# espurna-wd.net
KiCad netlist of a schematic drawn in EAGLE
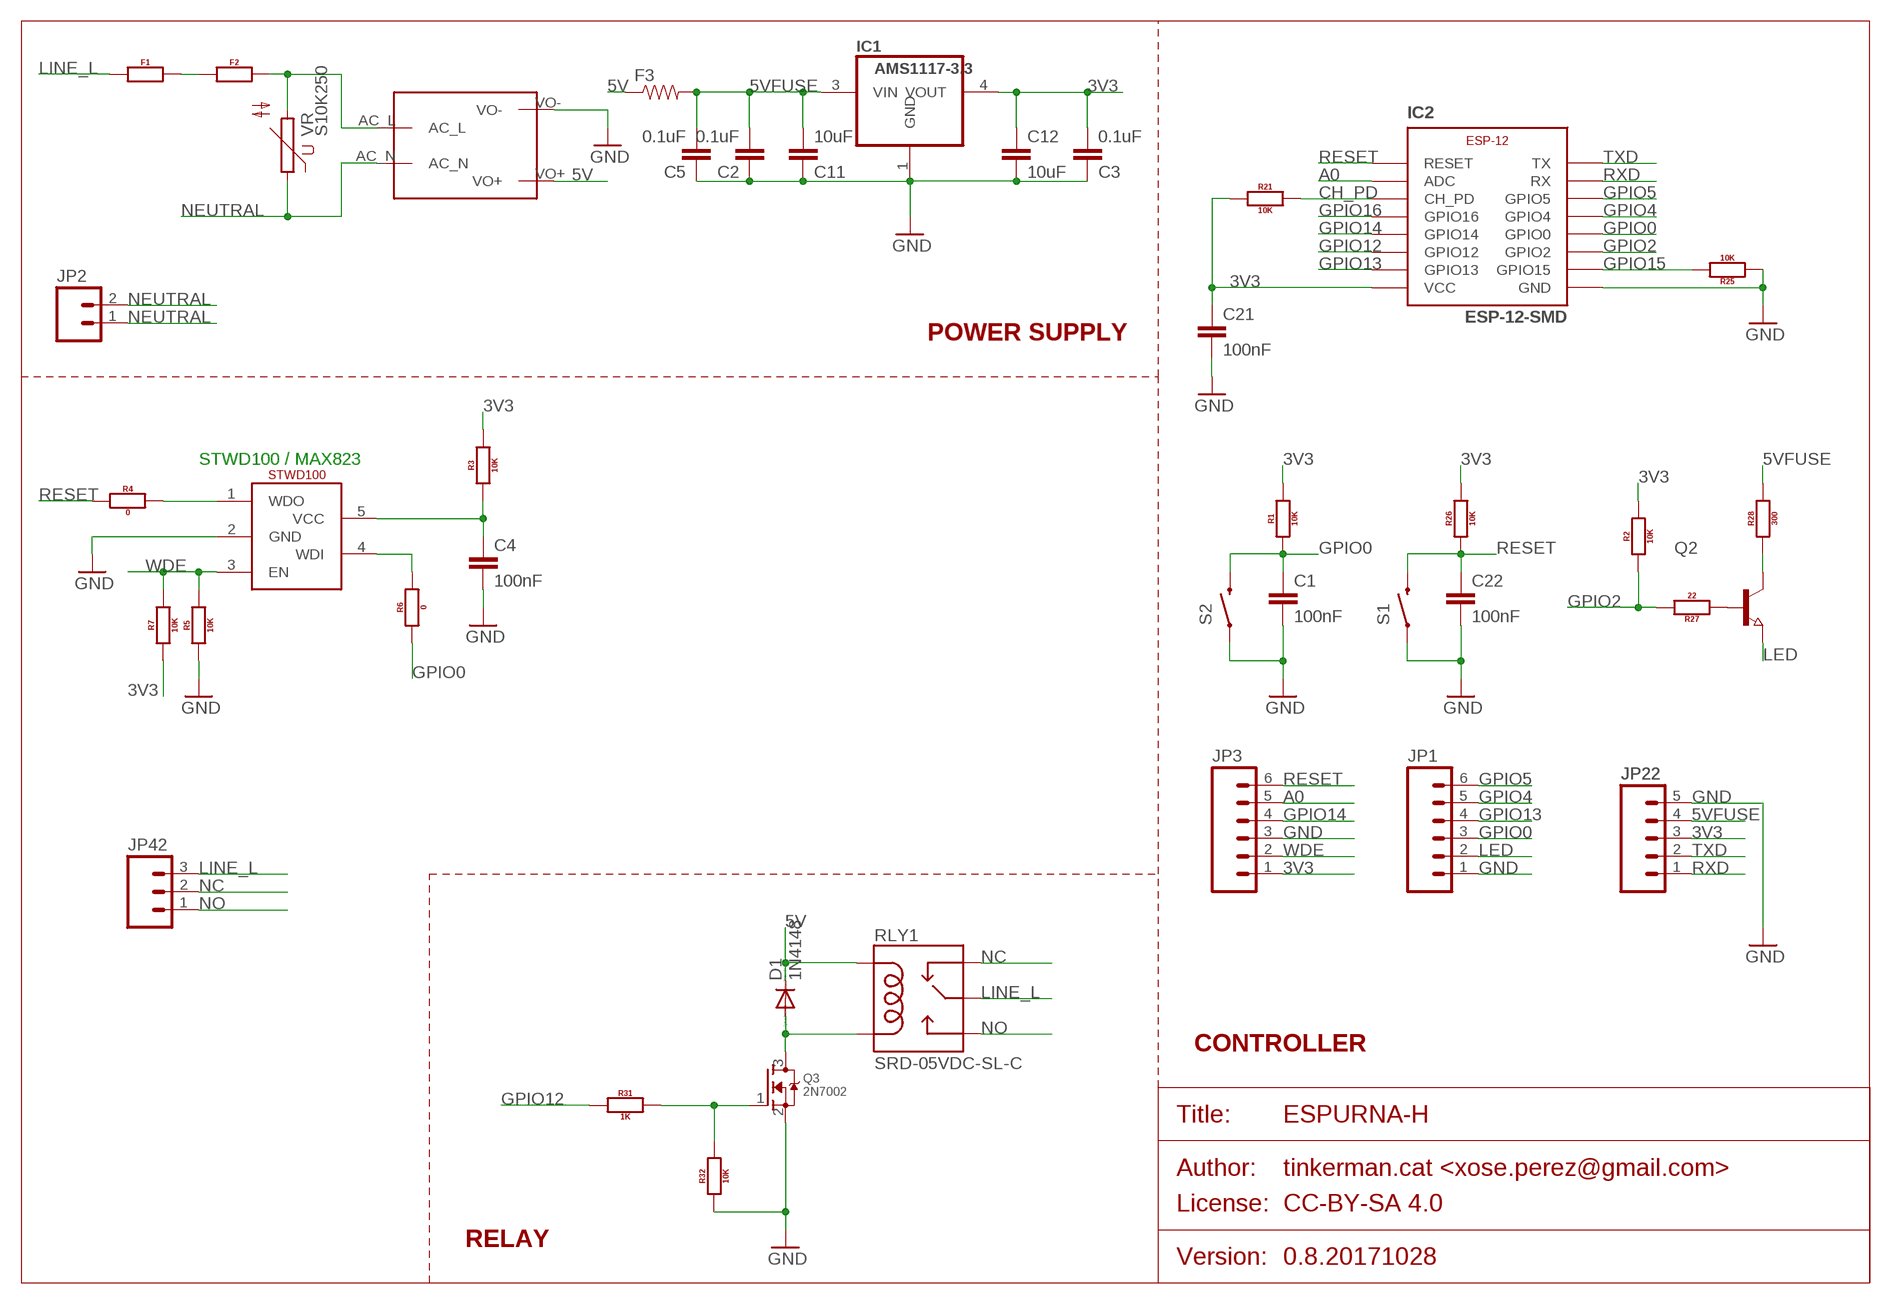
[diagram p0: schematic, sheet 1]

(export (version "E")
  (design (tool "Eeschema 10.0.6"))
  (components
    (comp (ref "C1")
      (value "100nF")
      (footprint "eagle-import:0805")
      (libsource (lib "eagle-import") (part "C-EU0805"))
    )
    (comp (ref "C2")
      (value "0.1uF")
      (footprint "eagle-import:C1206K")
      (libsource (lib "eagle-import") (part "C-EUC1206K"))
    )
    (comp (ref "C3")
      (value "0.1uF")
      (footprint "eagle-import:0805")
      (libsource (lib "eagle-import") (part "C-EU0805"))
    )
    (comp (ref "C4")
      (value "100nF")
      (footprint "eagle-import:0805")
      (libsource (lib "eagle-import") (part "C-EU0805"))
    )
    (comp (ref "C5")
      (value "0.1uF")
      (footprint "eagle-import:0805")
      (libsource (lib "eagle-import") (part "C-EU0805"))
    )
    (comp (ref "C11")
      (value "10uF")
      (footprint "eagle-import:C1206K")
      (libsource (lib "eagle-import") (part "C-EUC1206K"))
    )
    (comp (ref "C12")
      (value "10uF")
      (footprint "eagle-import:C1206")
      (libsource (lib "eagle-import") (part "C-EUC1206"))
    )
    (comp (ref "C21")
      (value "100nF")
      (footprint "eagle-import:0805")
      (libsource (lib "eagle-import") (part "C-EU0805"))
    )
    (comp (ref "C22")
      (value "100nF")
      (footprint "eagle-import:0805")
      (libsource (lib "eagle-import") (part "C-EU0805"))
    )
    (comp (ref "D1")
      (value "1N4148")
      (footprint "eagle-import:DO214BA")
      (libsource (lib "eagle-import") (part "DIODE-DO214BA"))
    )
    (comp (ref "F1")
      (value "THERMALFUSE0.4")
      (footprint "eagle-import:AXIAL-0.4")
      (libsource (lib "eagle-import") (part "THERMALFUSE0.4"))
    )
    (comp (ref "F2")
      (value "THERMALFUSE0.4")
      (footprint "eagle-import:AXIAL-0.4")
      (libsource (lib "eagle-import") (part "THERMALFUSE0.4"))
    )
    (comp (ref "F3")
      (value "RESISTOR1206")
      (footprint "eagle-import:1206")
      (libsource (lib "eagle-import") (part "RESISTOR1206"))
    )
    (comp (ref "IC1")
      (value "AMS1117-3.3")
      (footprint "eagle-import:SOT223")
      (libsource (lib "eagle-import") (part "REG1117SOT223-2"))
    )
    (comp (ref "IC2")
      (value "ESP-12-SMD")
      (footprint "eagle-import:ESP-12-SMD")
      (libsource (lib "eagle-import") (part "ESP-12-SMD"))
    )
    (comp (ref "JP1")
      (value "M06NO_SILK_FEMALE_PTH")
      (footprint "eagle-import:1X06_NO_SILK")
      (libsource (lib "eagle-import") (part "M06NO_SILK_FEMALE_PTH"))
    )
    (comp (ref "JP2")
      (value "M02200MIL")
      (footprint "eagle-import:SCREWTERMINAL-200MIL-2")
      (libsource (lib "eagle-import") (part "M02200MIL"))
    )
    (comp (ref "JP3")
      (value "M06NO_SILK_FEMALE_PTH")
      (footprint "eagle-import:1X06_NO_SILK")
      (libsource (lib "eagle-import") (part "M06NO_SILK_FEMALE_PTH"))
    )
    (comp (ref "JP22")
      (value "M05PTH")
      (footprint "eagle-import:1X05")
      (libsource (lib "eagle-import") (part "M05PTH"))
    )
    (comp (ref "JP42")
      (value "M03200MIL")
      (footprint "eagle-import:SCREWTERMINAL-200MIL-3")
      (libsource (lib "eagle-import") (part "M03200MIL"))
    )
    (comp (ref "Q2")
      (value "NPN-TRANSISTOR_SOT23")
      (footprint "eagle-import:SOT23")
      (libsource (lib "eagle-import") (part "NPN-TRANSISTOR_SOT23"))
    )
    (comp (ref "Q3")
      (value "2N7002")
      (footprint "eagle-import:SOT23")
      (libsource (lib "eagle-import") (part "MOSFET-NREFLOW"))
    )
    (comp (ref "R1")
      (value "10K")
      (footprint "eagle-import:0805")
      (libsource (lib "eagle-import") (part "RESISTOR0805"))
    )
    (comp (ref "R2")
      (value "10K")
      (footprint "eagle-import:0805")
      (libsource (lib "eagle-import") (part "RESISTOR0805"))
    )
    (comp (ref "R3")
      (value "10K")
      (footprint "eagle-import:0805")
      (libsource (lib "eagle-import") (part "RESISTOR0805"))
    )
    (comp (ref "R4")
      (value "0")
      (footprint "eagle-import:0805")
      (libsource (lib "eagle-import") (part "RESISTOR0805"))
    )
    (comp (ref "R5")
      (value "10K")
      (footprint "eagle-import:0805")
      (libsource (lib "eagle-import") (part "RESISTOR0805"))
    )
    (comp (ref "R6")
      (value "0")
      (footprint "eagle-import:0805")
      (libsource (lib "eagle-import") (part "RESISTOR0805"))
    )
    (comp (ref "R7")
      (value "10K")
      (footprint "eagle-import:0805")
      (libsource (lib "eagle-import") (part "RESISTOR0805"))
    )
    (comp (ref "R21")
      (value "10K")
      (footprint "eagle-import:0805")
      (libsource (lib "eagle-import") (part "RESISTOR0805"))
    )
    (comp (ref "R25")
      (value "10K")
      (footprint "eagle-import:0805")
      (libsource (lib "eagle-import") (part "RESISTOR0805"))
    )
    (comp (ref "R26")
      (value "10K")
      (footprint "eagle-import:0805")
      (libsource (lib "eagle-import") (part "RESISTOR0805"))
    )
    (comp (ref "R27")
      (value "22")
      (footprint "eagle-import:0805")
      (libsource (lib "eagle-import") (part "RESISTOR0805"))
    )
    (comp (ref "R28")
      (value "300")
      (footprint "eagle-import:0805")
      (libsource (lib "eagle-import") (part "RESISTOR0805"))
    )
    (comp (ref "R31")
      (value "1K")
      (footprint "eagle-import:0805")
      (libsource (lib "eagle-import") (part "RESISTOR0805"))
    )
    (comp (ref "R32")
      (value "10K")
      (footprint "eagle-import:0805")
      (libsource (lib "eagle-import") (part "RESISTOR0805"))
    )
    (comp (ref "RLY1")
      (value "SRD-05VDC-SL-C")
      (footprint "eagle-import:SRD-5VDC-SL-C")
      (libsource (lib "eagle-import") (part "RELAYSONGLE"))
    )
    (comp (ref "S1")
      (value "SWITCH-MOMENTARY-2SMD-1101NE")
      (footprint "eagle-import:TACTILE-SWITCH-1101NE")
      (libsource (lib "eagle-import") (part "SWITCH-MOMENTARY-2SMD-1101NE"))
    )
    (comp (ref "S2")
      (value "SWITCH-MOMENTARY-2SMD-1101NE")
      (footprint "eagle-import:TACTILE-SWITCH-1101NE")
      (libsource (lib "eagle-import") (part "SWITCH-MOMENTARY-2SMD-1101NE"))
    )
    (comp (ref "U$1")
      (value "MAINS_CONVERTERS")
      (footprint "eagle-import:HLK-PM01")
      (libsource (lib "eagle-import") (part "MAINS_CONVERTERS"))
    )
    (comp (ref "VR")
      (value "S10K250")
      (footprint "eagle-import:S10K250")
      (libsource (lib "eagle-import") (part "S10K250"))
    )
    (comp (ref "WD")
      (value "STWD100")
      (footprint "eagle-import:SOT95P280X145-5N")
      (libsource (lib "eagle-import") (part "STWD100"))
    )
  )
  (nets
    (net (code "1") (name "/3V3") (class "Default")
      (node (ref "C12") (pin "1") (pinfunction "1_1") (pintype "passive"))
      (node (ref "C21") (pin "1") (pinfunction "1_1") (pintype "passive"))
      (node (ref "C3") (pin "2") (pinfunction "2_2") (pintype "passive"))
      (node (ref "IC1") (pin "4") (pinfunction "VOUT_4") (pintype "output"))
      (node (ref "IC2") (pin "VCC") (pinfunction "VCC_VCC") (pintype "bidirectional"))
      (node (ref "JP22") (pin "3") (pinfunction "3_3") (pintype "passive"))
      (node (ref "JP3") (pin "1") (pinfunction "1_1") (pintype "passive"))
      (node (ref "R1") (pin "2") (pinfunction "2_2") (pintype "passive"))
      (node (ref "R2") (pin "2") (pinfunction "2_2") (pintype "passive"))
      (node (ref "R21") (pin "1") (pinfunction "1_1") (pintype "passive"))
      (node (ref "R26") (pin "2") (pinfunction "2_2") (pintype "passive"))
      (node (ref "R3") (pin "2") (pinfunction "2_2") (pintype "passive"))
      (node (ref "R7") (pin "1") (pinfunction "1_1") (pintype "passive"))
    )
    (net (code "2") (name "/5V") (class "Default")
      (node (ref "D1") (pin "C") (pinfunction "C_C") (pintype "passive"))
      (node (ref "F3") (pin "1") (pinfunction "1_1") (pintype "passive"))
      (node (ref "RLY1") (pin "COIL1") (pinfunction "COIL1_COIL1") (pintype "bidirectional"))
      (node (ref "U$1") (pin "VO+") (pinfunction "VO+_VO+") (pintype "output"))
    )
    (net (code "3") (name "/5VFUSE") (class "Default")
      (node (ref "C11") (pin "2") (pinfunction "2_2") (pintype "passive"))
      (node (ref "C2") (pin "2") (pinfunction "2_2") (pintype "passive"))
      (node (ref "C5") (pin "2") (pinfunction "2_2") (pintype "passive"))
      (node (ref "F3") (pin "2") (pinfunction "2_2") (pintype "passive"))
      (node (ref "IC1") (pin "3") (pinfunction "VIN_3") (pintype "input"))
      (node (ref "JP22") (pin "4") (pinfunction "4_4") (pintype "passive"))
      (node (ref "R28") (pin "2") (pinfunction "2_2") (pintype "passive"))
    )
    (net (code "4") (name "/A0") (class "Default")
      (node (ref "IC2") (pin "ADC") (pinfunction "ADC_ADC") (pintype "bidirectional"))
      (node (ref "JP3") (pin "5") (pinfunction "5_5") (pintype "passive"))
    )
    (net (code "5") (name "/CH_PD") (class "Default")
      (node (ref "IC2") (pin "CH_PD") (pinfunction "CH_PD_CH_PD") (pintype "bidirectional"))
      (node (ref "R21") (pin "2") (pinfunction "2_2") (pintype "passive"))
    )
    (net (code "6") (name "/GPIO0") (class "Default")
      (node (ref "C1") (pin "1") (pinfunction "1_1") (pintype "passive"))
      (node (ref "IC2") (pin "GPIO0") (pinfunction "GPIO0_GPIO0") (pintype "bidirectional"))
      (node (ref "JP1") (pin "3") (pinfunction "3_3") (pintype "passive"))
      (node (ref "R1") (pin "1") (pinfunction "1_1") (pintype "passive"))
      (node (ref "R6") (pin "1") (pinfunction "1_1") (pintype "passive"))
      (node (ref "S2") (pin "2") (pinfunction "2_2") (pintype "passive"))
    )
    (net (code "7") (name "/GPIO2") (class "Default")
      (node (ref "IC2") (pin "GPIO2") (pinfunction "GPIO2_GPIO2") (pintype "bidirectional"))
      (node (ref "R2") (pin "1") (pinfunction "1_1") (pintype "passive"))
      (node (ref "R27") (pin "2") (pinfunction "2_2") (pintype "passive"))
    )
    (net (code "8") (name "/GPIO4") (class "Default")
      (node (ref "IC2") (pin "GPIO4") (pinfunction "GPIO4_GPIO4") (pintype "bidirectional"))
      (node (ref "JP1") (pin "5") (pinfunction "5_5") (pintype "passive"))
    )
    (net (code "9") (name "/GPIO5") (class "Default")
      (node (ref "IC2") (pin "GPIO5") (pinfunction "GPIO5_GPIO5") (pintype "bidirectional"))
      (node (ref "JP1") (pin "6") (pinfunction "6_6") (pintype "passive"))
    )
    (net (code "10") (name "/GPIO12") (class "Default")
      (node (ref "IC2") (pin "GPIO12") (pinfunction "GPIO12_GPIO12") (pintype "bidirectional"))
      (node (ref "R31") (pin "1") (pinfunction "1_1") (pintype "passive"))
    )
    (net (code "11") (name "/GPIO13") (class "Default")
      (node (ref "IC2") (pin "GPIO13") (pinfunction "GPIO13_GPIO13") (pintype "bidirectional"))
      (node (ref "JP1") (pin "4") (pinfunction "4_4") (pintype "passive"))
    )
    (net (code "12") (name "/GPIO14") (class "Default")
      (node (ref "IC2") (pin "GPIO14") (pinfunction "GPIO14_GPIO14") (pintype "bidirectional"))
      (node (ref "JP3") (pin "4") (pinfunction "4_4") (pintype "passive"))
    )
    (net (code "13") (name "/GPIO15") (class "Default")
      (node (ref "IC2") (pin "GPIO15") (pinfunction "GPIO15_GPIO15") (pintype "bidirectional"))
      (node (ref "R25") (pin "2") (pinfunction "2_2") (pintype "passive"))
    )
    (net (code "14") (name "/GPIO16") (class "Default")
      (node (ref "IC2") (pin "GPIO16") (pinfunction "GPIO16_GPIO16") (pintype "bidirectional"))
    )
    (net (code "15") (name "/LED") (class "Default")
      (node (ref "JP1") (pin "2") (pinfunction "2_2") (pintype "passive"))
      (node (ref "Q2") (pin "2") (pinfunction "E_2") (pintype "passive"))
    )
    (net (code "16") (name "/LINE_L") (class "Default")
      (node (ref "F1") (pin "P$1") (pinfunction "1_P$1") (pintype "passive"))
      (node (ref "JP42") (pin "3") (pinfunction "3_3") (pintype "passive"))
      (node (ref "RLY1") (pin "COMMON") (pinfunction "MAIN_COMMON") (pintype "bidirectional"))
    )
    (net (code "17") (name "/NC") (class "Default")
      (node (ref "JP42") (pin "2") (pinfunction "2_2") (pintype "passive"))
      (node (ref "RLY1") (pin "CLOSED") (pinfunction "NC_CLOSED") (pintype "bidirectional"))
    )
    (net (code "18") (name "/NEUTRAL") (class "Default")
      (node (ref "JP2") (pin "1") (pinfunction "1_1") (pintype "passive"))
      (node (ref "JP2") (pin "2") (pinfunction "2_2") (pintype "passive"))
      (node (ref "U$1") (pin "AC_N") (pinfunction "AC_N_AC_N") (pintype "input"))
      (node (ref "VR") (pin "1") (pinfunction "1_1") (pintype "passive"))
    )
    (net (code "19") (name "/NO") (class "Default")
      (node (ref "JP42") (pin "1") (pinfunction "1_1") (pintype "passive"))
      (node (ref "RLY1") (pin "OPEN") (pinfunction "NO_OPEN") (pintype "bidirectional"))
    )
    (net (code "20") (name "/RESET") (class "Default")
      (node (ref "C22") (pin "1") (pinfunction "1_1") (pintype "passive"))
      (node (ref "IC2") (pin "RESET") (pinfunction "RESET_RESET") (pintype "bidirectional"))
      (node (ref "JP3") (pin "6") (pinfunction "6_6") (pintype "passive"))
      (node (ref "R26") (pin "1") (pinfunction "1_1") (pintype "passive"))
      (node (ref "R4") (pin "1") (pinfunction "1_1") (pintype "passive"))
      (node (ref "S1") (pin "2") (pinfunction "2_2") (pintype "passive"))
    )
    (net (code "21") (name "/RXD") (class "Default")
      (node (ref "IC2") (pin "RX") (pinfunction "RX_RX") (pintype "bidirectional"))
      (node (ref "JP22") (pin "1") (pinfunction "1_1") (pintype "passive"))
    )
    (net (code "22") (name "/TXD") (class "Default")
      (node (ref "IC2") (pin "TX") (pinfunction "TX_TX") (pintype "bidirectional"))
      (node (ref "JP22") (pin "2") (pinfunction "2_2") (pintype "passive"))
    )
    (net (code "23") (name "/WDE") (class "Default")
      (node (ref "JP3") (pin "2") (pinfunction "2_2") (pintype "passive"))
      (node (ref "R5") (pin "2") (pinfunction "2_2") (pintype "passive"))
      (node (ref "R7") (pin "2") (pinfunction "2_2") (pintype "passive"))
      (node (ref "WD") (pin "3") (pinfunction "EN_3") (pintype "bidirectional"))
    )
    (net (code "24") (name "GND") (class "Default")
      (node (ref "C1") (pin "2") (pinfunction "2_2") (pintype "passive"))
      (node (ref "C11") (pin "1") (pinfunction "1_1") (pintype "passive"))
      (node (ref "C12") (pin "2") (pinfunction "2_2") (pintype "passive"))
      (node (ref "C2") (pin "1") (pinfunction "1_1") (pintype "passive"))
      (node (ref "C21") (pin "2") (pinfunction "2_2") (pintype "passive"))
      (node (ref "C22") (pin "2") (pinfunction "2_2") (pintype "passive"))
      (node (ref "C3") (pin "1") (pinfunction "1_1") (pintype "passive"))
      (node (ref "C4") (pin "2") (pinfunction "2_2") (pintype "passive"))
      (node (ref "C5") (pin "1") (pinfunction "1_1") (pintype "passive"))
      (node (ref "IC1") (pin "1") (pinfunction "GND_1") (pintype "power_in"))
      (node (ref "IC2") (pin "GND") (pinfunction "GND_GND") (pintype "bidirectional"))
      (node (ref "JP1") (pin "1") (pinfunction "1_1") (pintype "passive"))
      (node (ref "JP22") (pin "5") (pinfunction "5_5") (pintype "passive"))
      (node (ref "JP3") (pin "3") (pinfunction "3_3") (pintype "passive"))
      (node (ref "Q3") (pin "2") (pinfunction "S_2") (pintype "bidirectional"))
      (node (ref "R25") (pin "1") (pinfunction "1_1") (pintype "passive"))
      (node (ref "R32") (pin "1") (pinfunction "1_1") (pintype "passive"))
      (node (ref "R5") (pin "1") (pinfunction "1_1") (pintype "passive"))
      (node (ref "S1") (pin "1") (pinfunction "1_1") (pintype "passive"))
      (node (ref "S2") (pin "1") (pinfunction "1_1") (pintype "passive"))
      (node (ref "U$1") (pin "VO-") (pinfunction "VO-_VO-") (pintype "output"))
      (node (ref "WD") (pin "2") (pinfunction "GND_2") (pintype "bidirectional"))
    )
    (net (code "25") (name "Net-(F1-2)") (class "Default")
      (node (ref "F1") (pin "P$2") (pinfunction "2_P$2") (pintype "passive"))
      (node (ref "F2") (pin "P$1") (pinfunction "1_P$1") (pintype "passive"))
    )
    (net (code "26") (name "Net-(F2-2)") (class "Default")
      (node (ref "F2") (pin "P$2") (pinfunction "2_P$2") (pintype "passive"))
      (node (ref "U$1") (pin "AC_L") (pinfunction "AC_L_AC_L") (pintype "input"))
      (node (ref "VR") (pin "2") (pinfunction "2_2") (pintype "passive"))
    )
    (net (code "27") (name "Net-(Q2-B)") (class "Default")
      (node (ref "Q2") (pin "1") (pinfunction "B_1") (pintype "passive"))
      (node (ref "R27") (pin "1") (pinfunction "1_1") (pintype "passive"))
    )
    (net (code "28") (name "Net-(Q2-C)") (class "Default")
      (node (ref "Q2") (pin "3") (pinfunction "C_3") (pintype "passive"))
      (node (ref "R28") (pin "1") (pinfunction "1_1") (pintype "passive"))
    )
    (net (code "29") (name "Net-(Q3-D)") (class "Default")
      (node (ref "D1") (pin "A") (pinfunction "A_A") (pintype "passive"))
      (node (ref "Q3") (pin "3") (pinfunction "D_3") (pintype "bidirectional"))
      (node (ref "RLY1") (pin "COIL2") (pinfunction "COIL2_COIL2") (pintype "bidirectional"))
    )
    (net (code "30") (name "Net-(Q3-G)") (class "Default")
      (node (ref "Q3") (pin "1") (pinfunction "G_1") (pintype "bidirectional"))
      (node (ref "R31") (pin "2") (pinfunction "2_2") (pintype "passive"))
      (node (ref "R32") (pin "2") (pinfunction "2_2") (pintype "passive"))
    )
    (net (code "31") (name "Net-(WD-VCC)") (class "Default")
      (node (ref "C4") (pin "1") (pinfunction "1_1") (pintype "passive"))
      (node (ref "R3") (pin "1") (pinfunction "1_1") (pintype "passive"))
      (node (ref "WD") (pin "5") (pinfunction "VCC_5") (pintype "bidirectional"))
    )
    (net (code "32") (name "Net-(WD-WDI)") (class "Default")
      (node (ref "R6") (pin "2") (pinfunction "2_2") (pintype "passive"))
      (node (ref "WD") (pin "4") (pinfunction "WDI_4") (pintype "bidirectional"))
    )
    (net (code "33") (name "Net-(WD-WDO)") (class "Default")
      (node (ref "R4") (pin "2") (pinfunction "2_2") (pintype "passive"))
      (node (ref "WD") (pin "1") (pinfunction "WDO_1") (pintype "bidirectional"))
    )
  )
)
